# IMU.net
KiCad netlist of a schematic drawn in Altium Designer
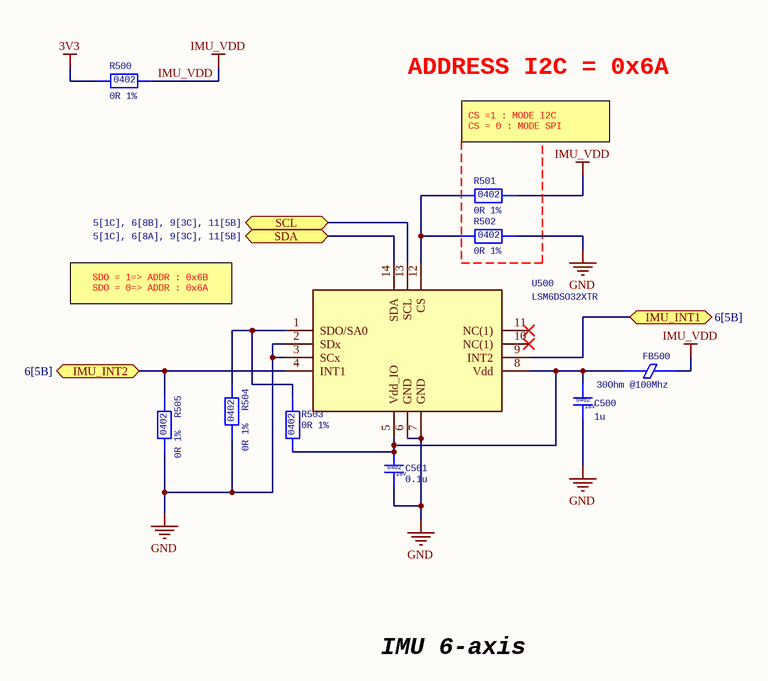
[diagram p0: IMU.SchDoc]

(export (version "E")
  (design (tool "Eeschema 10.0.6"))
  (components
    (comp (ref "C500")
      (value "1u")
      (footprint "CAP0402")
      (fields
        (field (name "MANUFACTURER") "Taiyo Yuden")
        (field (name "MANUFACTURER PART NUMBER") "EMK105BJ105KV-F")
      )
      (libsource (lib "Hw_Lib") (part "C_0402_1u"))
    )
    (comp (ref "C501")
      (value "0.1u")
      (footprint "CAP0402")
      (fields
        (field (name "MANUFACTURER") "Murata")
        (field (name "MANUFACTURER PART NUMBER") "GRM155R71C104KA88J")
      )
      (libsource (lib "Hw_Lib") (part "C_0402_0.1u"))
    )
    (comp (ref "FB500")
      (value "30Ohm @100Mhz")
      (footprint "FB0402")
      (description "Ferrite Chip, 1 Function(s), 1.4A, 2 Pin(s)")
      (fields
        (field (name "MANUFACTURER") "Murata")
        (field (name "MANUFACTURER PART NUMBER") "BLM15PD300SN1D")
      )
      (libsource (lib "Hw_Lib") (part "BLM15PD300SN1D"))
    )
    (comp (ref "R500")
      (value "0R 1%")
      (footprint "RES0402")
      (description "Metal Glaze/thick Film, 0.0625W, 0ohm, Surface Mount, 0402")
      (fields
        (field (name "MANUFACTURER") "Yageo")
        (field (name "MANUFACTURER PART NUMBER") "RC0402JR-070RL")
      )
      (libsource (lib "Hw_Lib") (part "R_0402_0R"))
    )
    (comp (ref "R501")
      (value "0R 1%")
      (footprint "RES0402")
      (description "Metal Glaze/thick Film, 0.0625W, 0ohm, Surface Mount, 0402")
      (fields
        (field (name "MANUFACTURER") "Yageo")
        (field (name "MANUFACTURER PART NUMBER") "RC0402JR-070RL")
      )
      (libsource (lib "Hw_Lib") (part "R_0402_0R"))
    )
    (comp (ref "R502")
      (value "0R 1%")
      (footprint "RES0402")
      (description "Metal Glaze/thick Film, 0.0625W, 0ohm, Surface Mount, 0402")
      (fields
        (field (name "MANUFACTURER") "Yageo")
        (field (name "MANUFACTURER PART NUMBER") "RC0402JR-070RL")
      )
      (libsource (lib "Hw_Lib") (part "R_0402_0R"))
    )
    (comp (ref "R503")
      (value "0R 1%")
      (footprint "RES0402")
      (description "Metal Glaze/thick Film, 0.0625W, 0ohm, Surface Mount, 0402")
      (fields
        (field (name "MANUFACTURER") "Yageo")
        (field (name "MANUFACTURER PART NUMBER") "RC0402JR-070RL")
      )
      (libsource (lib "Hw_Lib") (part "R_0402_0R"))
    )
    (comp (ref "R504")
      (value "0R 1%")
      (footprint "RES0402")
      (description "Metal Glaze/thick Film, 0.0625W, 0ohm, Surface Mount, 0402")
      (fields
        (field (name "MANUFACTURER") "Yageo")
        (field (name "MANUFACTURER PART NUMBER") "RC0402JR-070RL")
      )
      (libsource (lib "Hw_Lib") (part "R_0402_0R"))
    )
    (comp (ref "R505")
      (value "0R 1%")
      (footprint "RES0402")
      (description "Metal Glaze/thick Film, 0.0625W, 0ohm, Surface Mount, 0402")
      (fields
        (field (name "MANUFACTURER") "Yageo")
        (field (name "MANUFACTURER PART NUMBER") "RC0402JR-070RL")
      )
      (libsource (lib "Hw_Lib") (part "R_0402_0R"))
    )
    (comp (ref "U500")
      (value "LSM6DSO32XTR")
      (footprint "LSM6DSO32XTR")
      (description "Analog Circuit")
      (fields (field (name "MANUFACTURER") "STMicroelectronics"))
      (libsource (lib "Hw_Lib") (part "LSM6DSO32XTR"))
    )
  )
  (nets
    (net (code "1") (name "/IMU_INT1") (class "Default")
      (node (ref "U500") (pin "9") (pinfunction "INT2_9") (pintype "open_collector"))
    )
    (net (code "2") (name "/IMU_INT2") (class "Default")
      (node (ref "R505") (pin "2") (pinfunction "2_2") (pintype "passive"))
      (node (ref "U500") (pin "4") (pinfunction "INT1_4") (pintype "open_collector"))
    )
    (net (code "3") (name "/SCL") (class "Default")
      (node (ref "U500") (pin "13") (pinfunction "SCL_13") (pintype "open_collector"))
    )
    (net (code "4") (name "/SDA") (class "Default")
      (node (ref "U500") (pin "14") (pinfunction "SDA_14") (pintype "open_collector"))
    )
    (net (code "5") (name "3V3") (class "Default")
      (node (ref "R500") (pin "1") (pinfunction "1_1") (pintype "passive"))
    )
    (net (code "6") (name "GND") (class "Default")
      (node (ref "C500") (pin "2") (pinfunction "2_2") (pintype "passive"))
      (node (ref "C501") (pin "2") (pinfunction "2_2") (pintype "passive"))
      (node (ref "R502") (pin "2") (pinfunction "2_2") (pintype "passive"))
      (node (ref "R504") (pin "1") (pinfunction "1_1") (pintype "passive"))
      (node (ref "R505") (pin "1") (pinfunction "1_1") (pintype "passive"))
      (node (ref "U500") (pin "2") (pinfunction "SDx_2") (pintype "open_collector"))
      (node (ref "U500") (pin "3") (pinfunction "SCx_3") (pintype "open_collector"))
      (node (ref "U500") (pin "6") (pinfunction "GND_6") (pintype "open_collector"))
      (node (ref "U500") (pin "7") (pinfunction "GND_7") (pintype "open_collector"))
    )
    (net (code "7") (name "IMU_VDD") (class "Default")
      (node (ref "FB500") (pin "2") (pinfunction "2_2") (pintype "passive"))
      (node (ref "R500") (pin "2") (pinfunction "2_2") (pintype "passive"))
      (node (ref "R501") (pin "2") (pinfunction "2_2") (pintype "passive"))
    )
    (net (code "8") (name "Net-(U500-CS)") (class "Default")
      (node (ref "R501") (pin "1") (pinfunction "1_1") (pintype "passive"))
      (node (ref "R502") (pin "1") (pinfunction "1_1") (pintype "passive"))
      (node (ref "U500") (pin "12") (pinfunction "CS_12") (pintype "open_collector"))
    )
    (net (code "9") (name "Net-(U500-SDO{slash}SA0)") (class "Default")
      (node (ref "R503") (pin "2") (pinfunction "2_2") (pintype "passive"))
      (node (ref "R504") (pin "2") (pinfunction "2_2") (pintype "passive"))
      (node (ref "U500") (pin "1") (pinfunction "SDO/SA0_1") (pintype "open_collector"))
    )
    (net (code "10") (name "Net-(U500-Vdd)") (class "Default")
      (node (ref "C500") (pin "1") (pinfunction "1_1") (pintype "passive"))
      (node (ref "C501") (pin "1") (pinfunction "1_1") (pintype "passive"))
      (node (ref "FB500") (pin "1") (pinfunction "1_1") (pintype "passive"))
      (node (ref "R503") (pin "1") (pinfunction "1_1") (pintype "passive"))
      (node (ref "U500") (pin "5") (pinfunction "Vdd_IO_5") (pintype "open_collector"))
      (node (ref "U500") (pin "8") (pinfunction "Vdd_8") (pintype "open_collector"))
    )
    (net (code "11") (name "unconnected-(U500-NC(1)-Pad10)") (class "Default")
      (node (ref "U500") (pin "10") (pinfunction "NC(1)_10") (pintype "open_collector+no_connect"))
    )
    (net (code "12") (name "unconnected-(U500-NC(1)-Pad11)") (class "Default")
      (node (ref "U500") (pin "11") (pinfunction "NC(1)_11") (pintype "open_collector+no_connect"))
    )
  )
)
